# 7segement2digits1badidea-mk-4_2.net
KiCad netlist of a schematic drawn in EAGLE
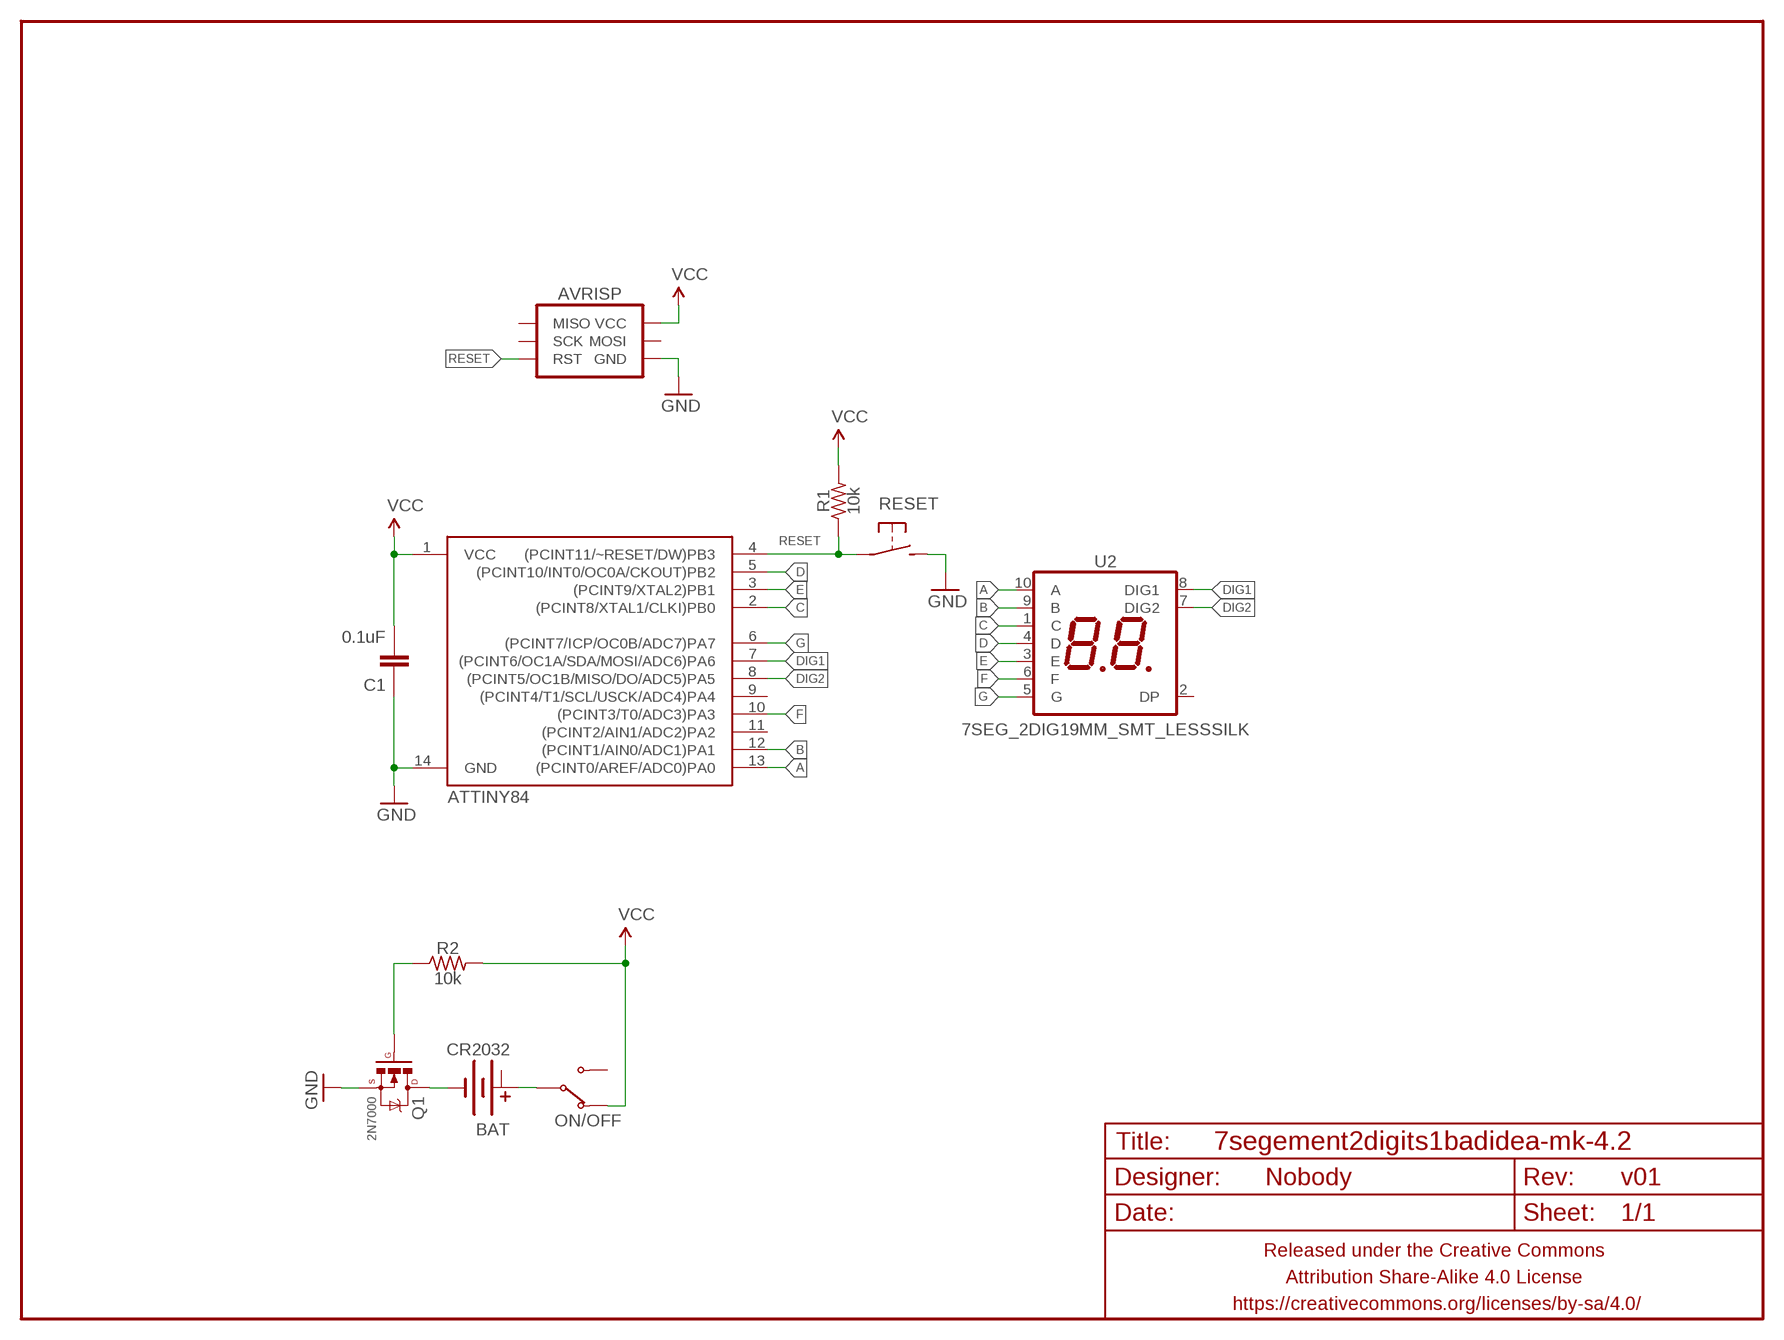
[diagram p0: schematic, sheet 1]

(export (version "E")
  (design (tool "Eeschema 10.0.6"))
  (components
    (comp (ref "AVRISP")
      (value "AVR_SPI_PRG_6PTH")
      (footprint "eagle-import:2X3")
      (libsource (lib "eagle-import") (part "AVR_SPI_PRG_6PTH"))
    )
    (comp (ref "BAT")
      (value "CR2032")
      (footprint "eagle-import:BATTCON_20MM_MINE_STAHPIT")
      (libsource (lib "eagle-import") (part "BATTERY-COINCR2032_SMD_TIGHT"))
    )
    (comp (ref "C1")
      (value "0.1uF")
      (footprint "eagle-import:C0805")
      (libsource (lib "eagle-import") (part "CAPACITOR-CERAMICC0805"))
    )
    (comp (ref "FRAME1")
      (value "FRAME-LETTERNO_PACKAGE")
      (footprint "eagle-import:DUMMY")
      (fields (field (name "DESIGNER") "Nobody"))
      (libsource (lib "eagle-import") (part "FRAME-LETTERNO_PACKAGE"))
    )
    (comp (ref "ON/OFF")
      (value "SWITCH-SPDTPTH-RA-2.54MM")
      (footprint "eagle-import:SPDT-RA-2.54MM")
      (libsource (lib "eagle-import") (part "SWITCH-SPDTPTH-RA-2.54MM"))
    )
    (comp (ref "Q1")
      (value "2N7000")
      (footprint "eagle-import:SOT23")
      (libsource (lib "eagle-import") (part "MOSFET-NCHANNELBSS123LT1G"))
    )
    (comp (ref "R1")
      (value "10k")
      (footprint "eagle-import:R0805")
      (libsource (lib "eagle-import") (part "RESISTORR0805"))
    )
    (comp (ref "R2")
      (value "10k")
      (footprint "eagle-import:R0805")
      (libsource (lib "eagle-import") (part "RESISTORR0805"))
    )
    (comp (ref "RESET")
      (value "SPST-NO-TACT3MM-RA")
      (footprint "eagle-import:TACTILE-PTH-SIDE")
      (libsource (lib "eagle-import") (part "SPST-NO-TACT3MM-RA"))
    )
    (comp (ref "U1")
      (value "ATTINY84")
      (footprint "eagle-import:SO14")
      (libsource (lib "eagle-import") (part "ATTINY84"))
    )
    (comp (ref "U2")
      (value "7SEG_2DIG19MM_SMT_LESSSILK")
      (footprint "eagle-import:7SEG_2DIG_19MM_SMT_LESSSILK")
      (libsource (lib "eagle-import") (part "7SEG_2DIG19MM_SMT_LESSSILK"))
    )
  )
  (nets
    (net (code "1") (name "A") (class "Default")
      (node (ref "U1") (pin "13") (pinfunction "(PCINT0/AREF/ADC0)PA0_13") (pintype "bidirectional"))
      (node (ref "U2") (pin "10") (pinfunction "A_10") (pintype "passive"))
    )
    (net (code "2") (name "B") (class "Default")
      (node (ref "U1") (pin "12") (pinfunction "(PCINT1/AIN0/ADC1)PA1_12") (pintype "bidirectional"))
      (node (ref "U2") (pin "9") (pinfunction "B_9") (pintype "passive"))
    )
    (net (code "3") (name "C") (class "Default")
      (node (ref "U1") (pin "2") (pinfunction "(PCINT8/XTAL1/CLKI)PB0_2") (pintype "bidirectional"))
      (node (ref "U2") (pin "1") (pinfunction "C_1") (pintype "passive"))
    )
    (net (code "4") (name "D") (class "Default")
      (node (ref "U1") (pin "5") (pinfunction "(PCINT10/INT0/OC0A/CKOUT)PB2_5") (pintype "bidirectional"))
      (node (ref "U2") (pin "4") (pinfunction "D_4") (pintype "passive"))
    )
    (net (code "5") (name "DIG1") (class "Default")
      (node (ref "U1") (pin "7") (pinfunction "(PCINT6/OC1A/SDA/MOSI/ADC6)PA6_7") (pintype "bidirectional"))
      (node (ref "U2") (pin "8") (pinfunction "DIG1_8") (pintype "passive"))
    )
    (net (code "6") (name "DIG2") (class "Default")
      (node (ref "U1") (pin "8") (pinfunction "(PCINT5/OC1B/MISO/DO/ADC5)PA5_8") (pintype "bidirectional"))
      (node (ref "U2") (pin "7") (pinfunction "DIG2_7") (pintype "passive"))
    )
    (net (code "7") (name "E") (class "Default")
      (node (ref "U1") (pin "3") (pinfunction "(PCINT9/XTAL2)PB1_3") (pintype "bidirectional"))
      (node (ref "U2") (pin "3") (pinfunction "E_3") (pintype "passive"))
    )
    (net (code "8") (name "F") (class "Default")
      (node (ref "U1") (pin "10") (pinfunction "(PCINT3/T0/ADC3)PA3_10") (pintype "bidirectional"))
      (node (ref "U2") (pin "6") (pinfunction "F_6") (pintype "passive"))
    )
    (net (code "9") (name "G") (class "Default")
      (node (ref "U1") (pin "6") (pinfunction "(PCINT7/ICP/OC0B/ADC7)PA7_6") (pintype "bidirectional"))
      (node (ref "U2") (pin "5") (pinfunction "G_5") (pintype "passive"))
    )
    (net (code "10") (name "GND") (class "Default")
      (node (ref "AVRISP") (pin "6") (pinfunction "GND_6") (pintype "passive"))
      (node (ref "C1") (pin "1") (pinfunction "1_1") (pintype "passive"))
      (node (ref "Q1") (pin "2") (pinfunction "S_2") (pintype "passive"))
      (node (ref "RESET") (pin "2") (pinfunction "2_2") (pintype "passive"))
      (node (ref "U1") (pin "14") (pinfunction "GND_14") (pintype "bidirectional"))
    )
    (net (code "11") (name "Net-(BAT-+)") (class "Default")
      (node (ref "BAT") (pin "TOP@1") (pinfunction "+_TOP@1") (pintype "bidirectional"))
      (node (ref "ON/OFF") (pin "2") (pinfunction "COM_2") (pintype "passive"))
    )
    (net (code "12") (name "Net-(BAT--)") (class "Default")
      (node (ref "BAT") (pin "BOTTOM") (pinfunction "-_BOTTOM") (pintype "bidirectional"))
      (node (ref "Q1") (pin "3") (pinfunction "D_3") (pintype "passive"))
    )
    (net (code "13") (name "Net-(Q1-G)") (class "Default")
      (node (ref "Q1") (pin "1") (pinfunction "G_1") (pintype "passive"))
      (node (ref "R2") (pin "1") (pinfunction "1_1") (pintype "passive"))
    )
    (net (code "14") (name "RESET") (class "Default")
      (node (ref "AVRISP") (pin "5") (pinfunction "RST_5") (pintype "passive"))
      (node (ref "R1") (pin "1") (pinfunction "1_1") (pintype "passive"))
      (node (ref "RESET") (pin "1") (pinfunction "1_1") (pintype "passive"))
      (node (ref "U1") (pin "4") (pinfunction "(PCINT11/~{RESET/DW})PB3_4") (pintype "bidirectional"))
    )
    (net (code "15") (name "VCC") (class "Default")
      (node (ref "AVRISP") (pin "2") (pinfunction "VCC_2") (pintype "passive"))
      (node (ref "C1") (pin "2") (pinfunction "2_2") (pintype "passive"))
      (node (ref "ON/OFF") (pin "1") (pinfunction "NC_1") (pintype "passive"))
      (node (ref "R1") (pin "2") (pinfunction "2_2") (pintype "passive"))
      (node (ref "R2") (pin "2") (pinfunction "2_2") (pintype "passive"))
      (node (ref "U1") (pin "1") (pinfunction "VCC_1") (pintype "bidirectional"))
    )
    (net (code "16") (name "unconnected-(AVRISP-MISO-Pad1)") (class "Default")
      (node (ref "AVRISP") (pin "1") (pinfunction "MISO_1") (pintype "passive"))
    )
    (net (code "17") (name "unconnected-(AVRISP-MOSI-Pad4)") (class "Default")
      (node (ref "AVRISP") (pin "4") (pinfunction "MOSI_4") (pintype "passive"))
    )
    (net (code "18") (name "unconnected-(AVRISP-SCK-Pad3)") (class "Default")
      (node (ref "AVRISP") (pin "3") (pinfunction "SCK_3") (pintype "passive"))
    )
    (net (code "19") (name "unconnected-(BAT-+1-PadTOP@2)") (class "Default")
      (node (ref "BAT") (pin "TOP@2") (pinfunction "+1_TOP@2") (pintype "bidirectional"))
    )
    (net (code "20") (name "unconnected-(ON/OFF-NO-Pad3)") (class "Default")
      (node (ref "ON/OFF") (pin "3") (pinfunction "NO_3") (pintype "passive"))
    )
    (net (code "21") (name "unconnected-(U1-(PCINT2{slash}AIN1{slash}ADC2)PA2-Pad11)") (class "Default")
      (node (ref "U1") (pin "11") (pinfunction "(PCINT2/AIN1/ADC2)PA2_11") (pintype "bidirectional"))
    )
    (net (code "22") (name "unconnected-(U1-(PCINT4{slash}T1{slash}SCL{slash}USCK{slash}ADC4)PA4-Pad9)") (class "Default")
      (node (ref "U1") (pin "9") (pinfunction "(PCINT4/T1/SCL/USCK/ADC4)PA4_9") (pintype "bidirectional"))
    )
    (net (code "23") (name "unconnected-(U2-DP-Pad2)") (class "Default")
      (node (ref "U2") (pin "2") (pinfunction "DP_2") (pintype "passive"))
    )
  )
)
